# SCH_TRAFFIC_LIGHT.net
KiCad netlist of a schematic drawn in Altium Designer
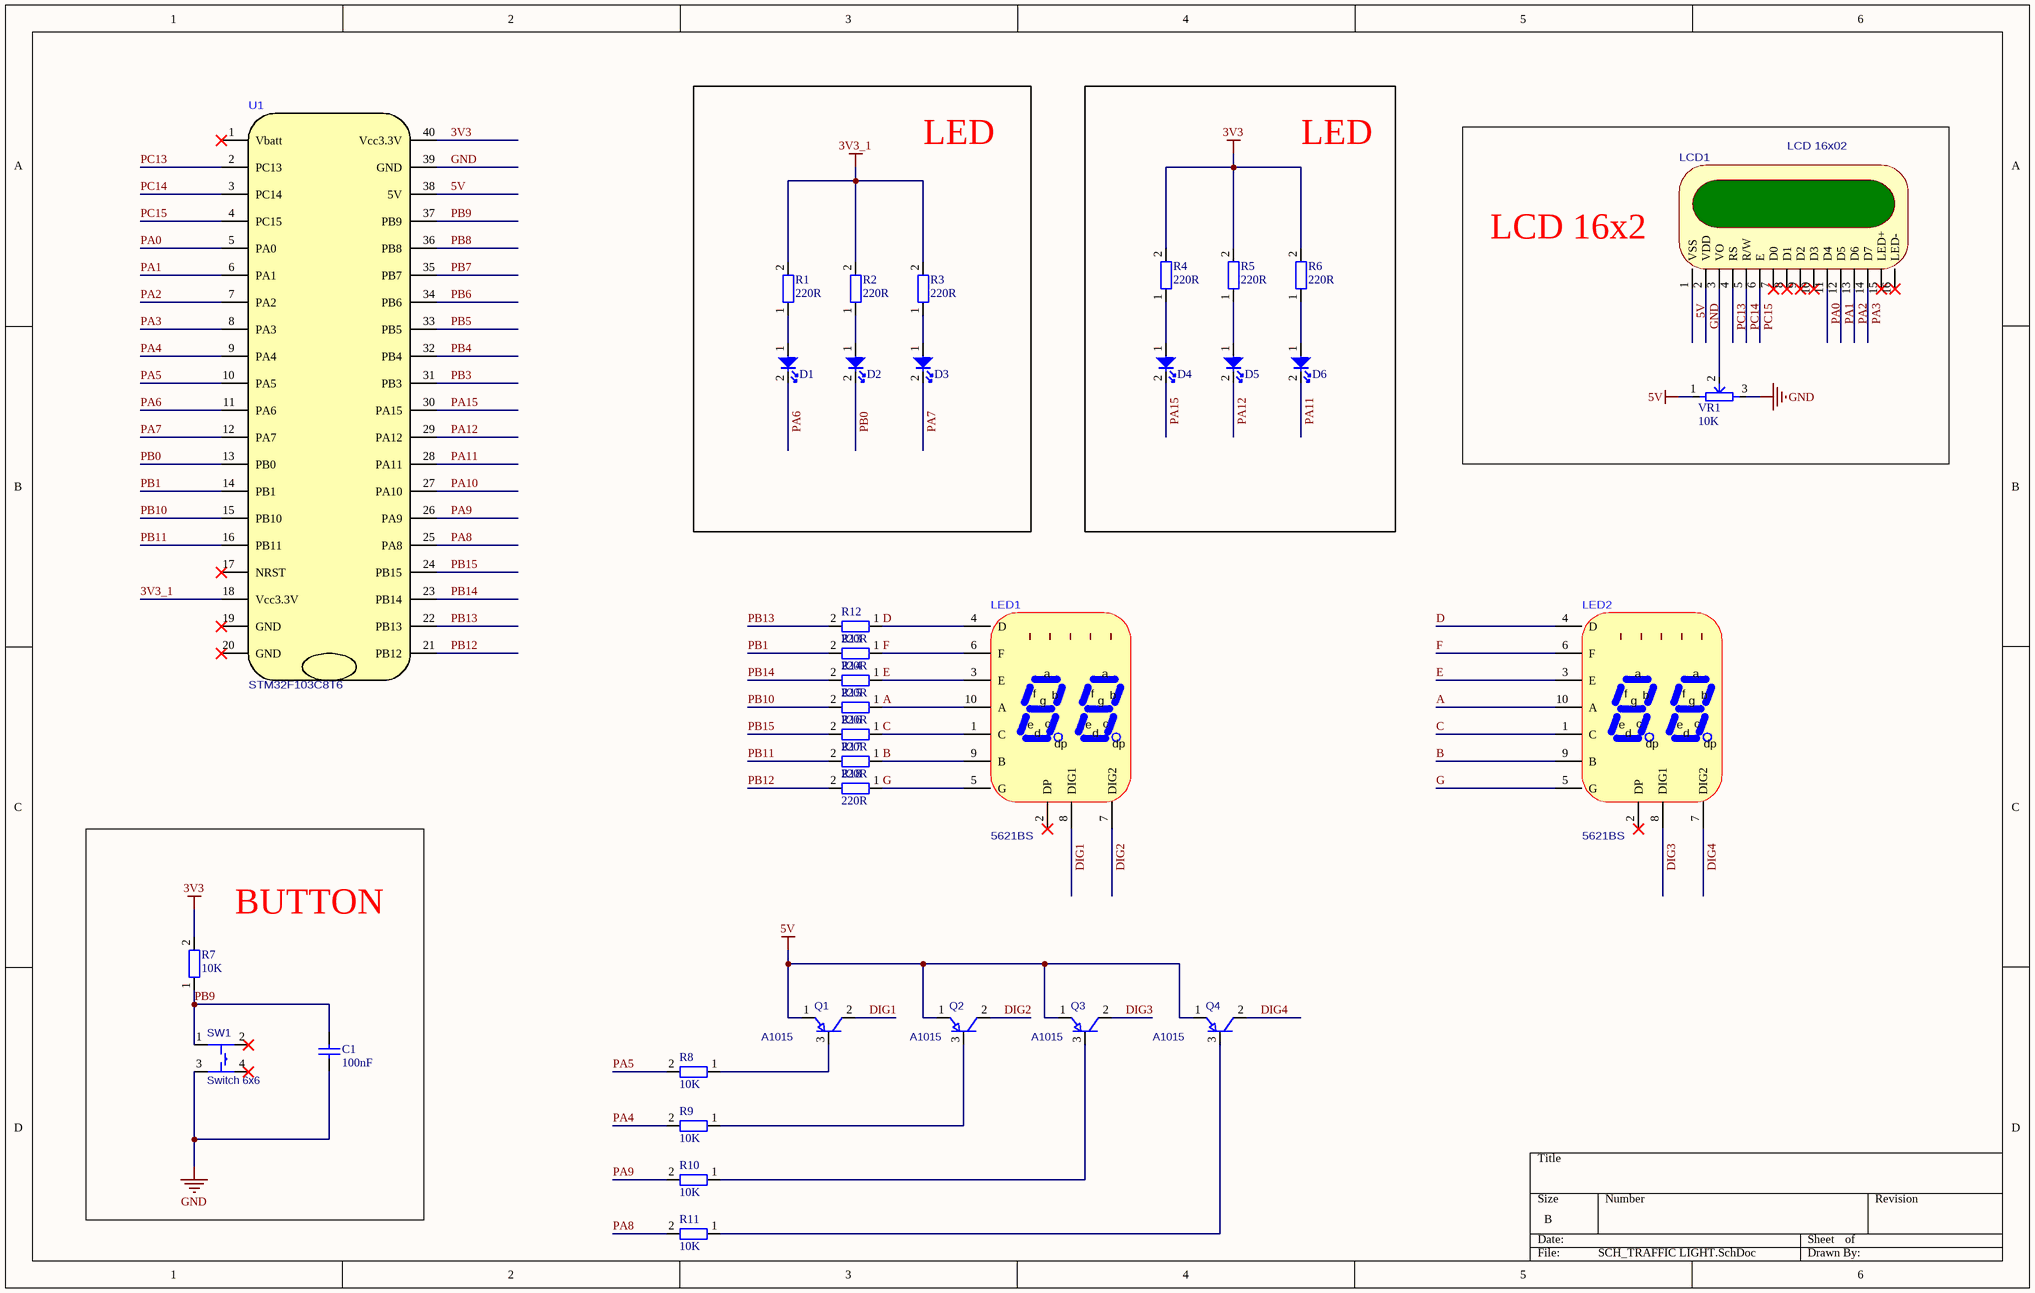
[diagram p0: SCH_TRAFFIC LIGHT.SchDoc]

(export (version "E")
  (design (tool "Eeschema 10.0.6"))
  (components
    (comp (ref "C1")
      (value "100nF")
      (footprint "CN1.5")
      (description "0805 Multilayer Ceramic Capacitors MLCC - SMD/SMT ROHS")
      (libsource (lib "SCH_AES_Library") (part "CAP 0805 50V 10%"))
    )
    (comp (ref "D1")
      (value "LED")
      (footprint "LED-3")
      (description "Emerald 0805 Light Emitting Diodes (LED) ROHS")
      (libsource (lib "SCH_AES_Library") (part "LED SMD 0805"))
    )
    (comp (ref "D2")
      (value "LED")
      (footprint "LED-3")
      (description "Emerald 0805 Light Emitting Diodes (LED) ROHS")
      (libsource (lib "SCH_AES_Library") (part "LED SMD 0805"))
    )
    (comp (ref "D3")
      (value "LED")
      (footprint "LED-3")
      (description "Emerald 0805 Light Emitting Diodes (LED) ROHS")
      (libsource (lib "SCH_AES_Library") (part "LED SMD 0805"))
    )
    (comp (ref "D4")
      (value "LED")
      (footprint "LED-3")
      (description "Emerald 0805 Light Emitting Diodes (LED) ROHS")
      (libsource (lib "SCH_AES_Library") (part "LED SMD 0805"))
    )
    (comp (ref "D5")
      (value "LED")
      (footprint "LED-3")
      (description "Emerald 0805 Light Emitting Diodes (LED) ROHS")
      (libsource (lib "SCH_AES_Library") (part "LED SMD 0805"))
    )
    (comp (ref "D6")
      (value "LED")
      (footprint "LED-3")
      (description "Emerald 0805 Light Emitting Diodes (LED) ROHS")
      (libsource (lib "SCH_AES_Library") (part "LED SMD 0805"))
    )
    (comp (ref "LCD1")
      (value "LCD 16x02")
      (footprint "LCD DISPLAYS 16X2")
      (description "LCD Displays Modules 16x02 5V ROHS")
      (libsource (lib "SCH_AES_Library") (part "LCD DISPLAYS 16x02"))
    )
    (comp (ref "LED1")
      (value "5621BS")
      (footprint "LED 7 SEG-2 0.56 inch")
      (libsource (lib "SCH_AES_Library") (part "LED 7 SEG -2 0.56 inch"))
    )
    (comp (ref "LED2")
      (value "5621BS")
      (footprint "LED 7 SEG-2 0.56 inch")
      (libsource (lib "SCH_AES_Library") (part "LED 7 SEG -2 0.56 inch"))
    )
    (comp (ref "Q1")
      (value "A1015")
      (footprint "TO-92")
      (fields
        (field (name "BOM_MANUFACTURER PART") "2SA1015-TA")
        (field (name "BOM_SUPPLIER PART") "C2084")
        (field (name "CONTRIBUTOR") "立创EDA官方封装库")
      )
      (libsource (lib "SCH_AES_Library") (part "TRANSISTOR HOLD PNP"))
    )
    (comp (ref "Q2")
      (value "A1015")
      (footprint "TO-92")
      (fields
        (field (name "BOM_MANUFACTURER PART") "2SA1015-TA")
        (field (name "BOM_SUPPLIER PART") "C2084")
        (field (name "CONTRIBUTOR") "立创EDA官方封装库")
      )
      (libsource (lib "SCH_AES_Library") (part "TRANSISTOR HOLD PNP"))
    )
    (comp (ref "Q3")
      (value "A1015")
      (footprint "TO-92")
      (fields
        (field (name "BOM_MANUFACTURER PART") "2SA1015-TA")
        (field (name "BOM_SUPPLIER PART") "C2084")
        (field (name "CONTRIBUTOR") "立创EDA官方封装库")
      )
      (libsource (lib "SCH_AES_Library") (part "TRANSISTOR HOLD PNP"))
    )
    (comp (ref "Q4")
      (value "A1015")
      (footprint "TO-92")
      (fields
        (field (name "BOM_MANUFACTURER PART") "2SA1015-TA")
        (field (name "BOM_SUPPLIER PART") "C2084")
        (field (name "CONTRIBUTOR") "立创EDA官方封装库")
      )
      (libsource (lib "SCH_AES_Library") (part "TRANSISTOR HOLD PNP"))
    )
    (comp (ref "R1")
      (value "220R")
      (footprint "RES CHIPS HOLD 1/4W TYPE 350MIL")
      (libsource (lib "SCH_AES_Library") (part "RES HOLD 1%"))
    )
    (comp (ref "R2")
      (value "220R")
      (footprint "RES CHIPS HOLD 1/4W TYPE 350MIL")
      (libsource (lib "SCH_AES_Library") (part "RES HOLD 1%"))
    )
    (comp (ref "R3")
      (value "220R")
      (footprint "RES CHIPS HOLD 1/4W TYPE 350MIL")
      (libsource (lib "SCH_AES_Library") (part "RES HOLD 1%"))
    )
    (comp (ref "R4")
      (value "220R")
      (footprint "RES CHIPS HOLD 1/4W TYPE 350MIL")
      (libsource (lib "SCH_AES_Library") (part "RES HOLD 1%"))
    )
    (comp (ref "R5")
      (value "220R")
      (footprint "RES CHIPS HOLD 1/4W TYPE 350MIL")
      (libsource (lib "SCH_AES_Library") (part "RES HOLD 1%"))
    )
    (comp (ref "R6")
      (value "220R")
      (footprint "RES CHIPS HOLD 1/4W TYPE 350MIL")
      (libsource (lib "SCH_AES_Library") (part "RES HOLD 1%"))
    )
    (comp (ref "R7")
      (value "10K")
      (footprint "RES CHIPS HOLD 1/4W TYPE 350MIL")
      (libsource (lib "SCH_AES_Library") (part "RES HOLD 1%"))
    )
    (comp (ref "R8")
      (value "10K")
      (footprint "RES CHIPS HOLD 1/4W TYPE 350MIL")
      (libsource (lib "SCH_AES_Library") (part "RES HOLD 1%"))
    )
    (comp (ref "R9")
      (value "10K")
      (footprint "RES CHIPS HOLD 1/4W TYPE 350MIL")
      (libsource (lib "SCH_AES_Library") (part "RES HOLD 1%"))
    )
    (comp (ref "R10")
      (value "10K")
      (footprint "RES CHIPS HOLD 1/4W TYPE 350MIL")
      (libsource (lib "SCH_AES_Library") (part "RES HOLD 1%"))
    )
    (comp (ref "R11")
      (value "10K")
      (footprint "RES CHIPS HOLD 1/4W TYPE 350MIL")
      (libsource (lib "SCH_AES_Library") (part "RES HOLD 1%"))
    )
    (comp (ref "R12")
      (value "220R")
      (footprint "RES CHIPS HOLD 1/4W TYPE 350MIL")
      (libsource (lib "SCH_AES_Library") (part "RES HOLD 1%"))
    )
    (comp (ref "R13")
      (value "220R")
      (footprint "RES CHIPS HOLD 1/4W TYPE 350MIL")
      (libsource (lib "SCH_AES_Library") (part "RES HOLD 1%"))
    )
    (comp (ref "R14")
      (value "220R")
      (footprint "RES CHIPS HOLD 1/4W TYPE 350MIL")
      (libsource (lib "SCH_AES_Library") (part "RES HOLD 1%"))
    )
    (comp (ref "R15")
      (value "220R")
      (footprint "RES CHIPS HOLD 1/4W TYPE 350MIL")
      (libsource (lib "SCH_AES_Library") (part "RES HOLD 1%"))
    )
    (comp (ref "R16")
      (value "220R")
      (footprint "RES CHIPS HOLD 1/4W TYPE 350MIL")
      (libsource (lib "SCH_AES_Library") (part "RES HOLD 1%"))
    )
    (comp (ref "R17")
      (value "220R")
      (footprint "RES CHIPS HOLD 1/4W TYPE 350MIL")
      (libsource (lib "SCH_AES_Library") (part "RES HOLD 1%"))
    )
    (comp (ref "R18")
      (value "220R")
      (footprint "RES CHIPS HOLD 1/4W TYPE 350MIL")
      (libsource (lib "SCH_AES_Library") (part "RES HOLD 1%"))
    )
    (comp (ref "SW1")
      (value "Switch 6x6")
      (footprint "SWITCHES TACTILE DIP 6X6x5 mm")
      (fields
        (field (name "BOM_MANUFACTURER PART") "B3F-1000")
        (field (name "BOM_SUPPLIER PART") "C93157")
        (field (name "CONTRIBUTOR") "LCSC")
      )
      (libsource (lib "SCH_AES_Library") (part "SWITCHS TACTILE DIP 6x6mm"))
    )
    (comp (ref "U1")
      (value "STM32F103C8T6")
      (footprint "MODULE STM32F103C8T6")
      (libsource (lib "SCH_AES_Library") (part "MODULE STM32F103C8T6"))
    )
    (comp (ref "VR1")
      (value "10K")
      (footprint "RES VARIABLE HOLE 3362P")
      (description "Plugin Variable Resistors/Potentiometers ROHS")
      (libsource (lib "SCH_AES_Library") (part "RES VARIABLE HOLD 3P"))
    )
  )
  (nets
    (net (code "1") (name "/A") (class "Default")
      (node (ref "LED1") (pin "10") (pinfunction "A_10") (pintype "passive"))
      (node (ref "LED2") (pin "10") (pinfunction "A_10") (pintype "passive"))
      (node (ref "R15") (pin "1") (pinfunction "1_1") (pintype "passive"))
    )
    (net (code "2") (name "/B") (class "Default")
      (node (ref "LED1") (pin "9") (pinfunction "B_9") (pintype "passive"))
      (node (ref "LED2") (pin "9") (pinfunction "B_9") (pintype "passive"))
      (node (ref "R17") (pin "1") (pinfunction "1_1") (pintype "passive"))
    )
    (net (code "3") (name "/C") (class "Default")
      (node (ref "LED1") (pin "1") (pinfunction "C_1") (pintype "passive"))
      (node (ref "LED2") (pin "1") (pinfunction "C_1") (pintype "passive"))
      (node (ref "R16") (pin "1") (pinfunction "1_1") (pintype "passive"))
    )
    (net (code "4") (name "/D") (class "Default")
      (node (ref "LED1") (pin "4") (pinfunction "D_4") (pintype "passive"))
      (node (ref "LED2") (pin "4") (pinfunction "D_4") (pintype "passive"))
      (node (ref "R12") (pin "1") (pinfunction "1_1") (pintype "passive"))
    )
    (net (code "5") (name "/DIG1") (class "Default")
      (node (ref "LED1") (pin "8") (pinfunction "DIG1_8") (pintype "passive"))
      (node (ref "Q1") (pin "2") (pinfunction "C_2") (pintype "passive"))
    )
    (net (code "6") (name "/DIG2") (class "Default")
      (node (ref "LED1") (pin "7") (pinfunction "DIG2_7") (pintype "passive"))
      (node (ref "Q2") (pin "2") (pinfunction "C_2") (pintype "passive"))
    )
    (net (code "7") (name "/DIG3") (class "Default")
      (node (ref "LED2") (pin "8") (pinfunction "DIG1_8") (pintype "passive"))
      (node (ref "Q3") (pin "2") (pinfunction "C_2") (pintype "passive"))
    )
    (net (code "8") (name "/DIG4") (class "Default")
      (node (ref "LED2") (pin "7") (pinfunction "DIG2_7") (pintype "passive"))
      (node (ref "Q4") (pin "2") (pinfunction "C_2") (pintype "passive"))
    )
    (net (code "9") (name "/E") (class "Default")
      (node (ref "LED1") (pin "3") (pinfunction "E_3") (pintype "passive"))
      (node (ref "LED2") (pin "3") (pinfunction "E_3") (pintype "passive"))
      (node (ref "R14") (pin "1") (pinfunction "1_1") (pintype "passive"))
    )
    (net (code "10") (name "/F") (class "Default")
      (node (ref "LED1") (pin "6") (pinfunction "F_6") (pintype "passive"))
      (node (ref "LED2") (pin "6") (pinfunction "F_6") (pintype "passive"))
      (node (ref "R13") (pin "1") (pinfunction "1_1") (pintype "passive"))
    )
    (net (code "11") (name "/G") (class "Default")
      (node (ref "LED1") (pin "5") (pinfunction "G_5") (pintype "passive"))
      (node (ref "LED2") (pin "5") (pinfunction "G_5") (pintype "passive"))
      (node (ref "R18") (pin "1") (pinfunction "1_1") (pintype "passive"))
    )
    (net (code "12") (name "/PA0") (class "Default")
      (node (ref "LCD1") (pin "11") (pinfunction "D4_11") (pintype "passive"))
      (node (ref "U1") (pin "5") (pinfunction "PA0_5") (pintype "passive"))
    )
    (net (code "13") (name "/PA1") (class "Default")
      (node (ref "LCD1") (pin "12") (pinfunction "D5_12") (pintype "passive"))
      (node (ref "U1") (pin "6") (pinfunction "PA1_6") (pintype "passive"))
    )
    (net (code "14") (name "/PA2") (class "Default")
      (node (ref "LCD1") (pin "13") (pinfunction "D6_13") (pintype "passive"))
      (node (ref "U1") (pin "7") (pinfunction "PA2_7") (pintype "passive"))
    )
    (net (code "15") (name "/PA3") (class "Default")
      (node (ref "LCD1") (pin "14") (pinfunction "D7_14") (pintype "passive"))
      (node (ref "U1") (pin "8") (pinfunction "PA3_8") (pintype "passive"))
    )
    (net (code "16") (name "/PA4") (class "Default")
      (node (ref "R9") (pin "2") (pinfunction "2_2") (pintype "passive"))
      (node (ref "U1") (pin "9") (pinfunction "PA4_9") (pintype "passive"))
    )
    (net (code "17") (name "/PA5") (class "Default")
      (node (ref "R8") (pin "2") (pinfunction "2_2") (pintype "passive"))
      (node (ref "U1") (pin "10") (pinfunction "PA5_10") (pintype "passive"))
    )
    (net (code "18") (name "/PA6") (class "Default")
      (node (ref "D1") (pin "2") (pinfunction "2_2") (pintype "passive"))
      (node (ref "U1") (pin "11") (pinfunction "PA6_11") (pintype "passive"))
    )
    (net (code "19") (name "/PA7") (class "Default")
      (node (ref "D3") (pin "2") (pinfunction "2_2") (pintype "passive"))
      (node (ref "U1") (pin "12") (pinfunction "PA7_12") (pintype "passive"))
    )
    (net (code "20") (name "/PA8") (class "Default")
      (node (ref "R11") (pin "2") (pinfunction "2_2") (pintype "passive"))
      (node (ref "U1") (pin "25") (pinfunction "PA8_25") (pintype "passive"))
    )
    (net (code "21") (name "/PA9") (class "Default")
      (node (ref "R10") (pin "2") (pinfunction "2_2") (pintype "passive"))
      (node (ref "U1") (pin "26") (pinfunction "PA9_26") (pintype "passive"))
    )
    (net (code "22") (name "/PA10") (class "Default")
      (node (ref "U1") (pin "27") (pinfunction "PA10_27") (pintype "passive"))
    )
    (net (code "23") (name "/PA11") (class "Default")
      (node (ref "D6") (pin "2") (pinfunction "2_2") (pintype "passive"))
      (node (ref "U1") (pin "28") (pinfunction "PA11_28") (pintype "passive"))
    )
    (net (code "24") (name "/PA12") (class "Default")
      (node (ref "D5") (pin "2") (pinfunction "2_2") (pintype "passive"))
      (node (ref "U1") (pin "29") (pinfunction "PA12_29") (pintype "passive"))
    )
    (net (code "25") (name "/PA15") (class "Default")
      (node (ref "D4") (pin "2") (pinfunction "2_2") (pintype "passive"))
      (node (ref "U1") (pin "30") (pinfunction "PA15_30") (pintype "passive"))
    )
    (net (code "26") (name "/PB0") (class "Default")
      (node (ref "D2") (pin "2") (pinfunction "2_2") (pintype "passive"))
      (node (ref "U1") (pin "13") (pinfunction "PB0_13") (pintype "passive"))
    )
    (net (code "27") (name "/PB1") (class "Default")
      (node (ref "R13") (pin "2") (pinfunction "2_2") (pintype "passive"))
      (node (ref "U1") (pin "14") (pinfunction "PB1_14") (pintype "passive"))
    )
    (net (code "28") (name "/PB3") (class "Default")
      (node (ref "U1") (pin "31") (pinfunction "PB3_31") (pintype "passive"))
    )
    (net (code "29") (name "/PB4") (class "Default")
      (node (ref "U1") (pin "32") (pinfunction "PB4_32") (pintype "passive"))
    )
    (net (code "30") (name "/PB5") (class "Default")
      (node (ref "U1") (pin "33") (pinfunction "PB5_33") (pintype "passive"))
    )
    (net (code "31") (name "/PB6") (class "Default")
      (node (ref "U1") (pin "34") (pinfunction "PB6_34") (pintype "passive"))
    )
    (net (code "32") (name "/PB7") (class "Default")
      (node (ref "U1") (pin "35") (pinfunction "PB7_35") (pintype "passive"))
    )
    (net (code "33") (name "/PB8") (class "Default")
      (node (ref "U1") (pin "36") (pinfunction "PB8_36") (pintype "passive"))
    )
    (net (code "34") (name "/PB9") (class "Default")
      (node (ref "C1") (pin "1") (pinfunction "1_1") (pintype "passive"))
      (node (ref "R7") (pin "1") (pinfunction "1_1") (pintype "passive"))
      (node (ref "SW1") (pin "1") (pinfunction "1_1") (pintype "passive"))
      (node (ref "U1") (pin "37") (pinfunction "PB9_37") (pintype "passive"))
    )
    (net (code "35") (name "/PB10") (class "Default")
      (node (ref "R15") (pin "2") (pinfunction "2_2") (pintype "passive"))
      (node (ref "U1") (pin "15") (pinfunction "PB10_15") (pintype "passive"))
    )
    (net (code "36") (name "/PB11") (class "Default")
      (node (ref "R17") (pin "2") (pinfunction "2_2") (pintype "passive"))
      (node (ref "U1") (pin "16") (pinfunction "PB11_16") (pintype "passive"))
    )
    (net (code "37") (name "/PB12") (class "Default")
      (node (ref "R18") (pin "2") (pinfunction "2_2") (pintype "passive"))
      (node (ref "U1") (pin "21") (pinfunction "PB12_21") (pintype "passive"))
    )
    (net (code "38") (name "/PB13") (class "Default")
      (node (ref "R12") (pin "2") (pinfunction "2_2") (pintype "passive"))
      (node (ref "U1") (pin "22") (pinfunction "PB13_22") (pintype "passive"))
    )
    (net (code "39") (name "/PB14") (class "Default")
      (node (ref "R14") (pin "2") (pinfunction "2_2") (pintype "passive"))
      (node (ref "U1") (pin "23") (pinfunction "PB14_23") (pintype "passive"))
    )
    (net (code "40") (name "/PB15") (class "Default")
      (node (ref "R16") (pin "2") (pinfunction "2_2") (pintype "passive"))
      (node (ref "U1") (pin "24") (pinfunction "PB15_24") (pintype "passive"))
    )
    (net (code "41") (name "/PC13") (class "Default")
      (node (ref "LCD1") (pin "4") (pinfunction "RS_4") (pintype "passive"))
      (node (ref "U1") (pin "2") (pinfunction "PC13_2") (pintype "passive"))
    )
    (net (code "42") (name "/PC14") (class "Default")
      (node (ref "LCD1") (pin "5") (pinfunction "R/W_5") (pintype "passive"))
      (node (ref "U1") (pin "3") (pinfunction "PC14_3") (pintype "passive"))
    )
    (net (code "43") (name "/PC15") (class "Default")
      (node (ref "LCD1") (pin "6") (pinfunction "E_6") (pintype "passive"))
      (node (ref "U1") (pin "4") (pinfunction "PC15_4") (pintype "passive"))
    )
    (net (code "44") (name "3V3") (class "Default")
      (node (ref "R4") (pin "2") (pinfunction "2_2") (pintype "passive"))
      (node (ref "R5") (pin "2") (pinfunction "2_2") (pintype "passive"))
      (node (ref "R6") (pin "2") (pinfunction "2_2") (pintype "passive"))
      (node (ref "R7") (pin "2") (pinfunction "2_2") (pintype "passive"))
      (node (ref "U1") (pin "40") (pinfunction "Vcc3.3V_40") (pintype "passive"))
    )
    (net (code "45") (name "3V3_1") (class "Default")
      (node (ref "R1") (pin "2") (pinfunction "2_2") (pintype "passive"))
      (node (ref "R2") (pin "2") (pinfunction "2_2") (pintype "passive"))
      (node (ref "R3") (pin "2") (pinfunction "2_2") (pintype "passive"))
      (node (ref "U1") (pin "18") (pinfunction "Vcc3.3V_18") (pintype "passive"))
    )
    (net (code "46") (name "5V") (class "Default")
      (node (ref "LCD1") (pin "1") (pinfunction "VSS_1") (pintype "passive"))
      (node (ref "Q1") (pin "1") (pinfunction "E_1") (pintype "passive"))
      (node (ref "Q2") (pin "1") (pinfunction "E_1") (pintype "passive"))
      (node (ref "Q3") (pin "1") (pinfunction "E_1") (pintype "passive"))
      (node (ref "Q4") (pin "1") (pinfunction "E_1") (pintype "passive"))
      (node (ref "U1") (pin "38") (pinfunction "5V_38") (pintype "passive"))
      (node (ref "VR1") (pin "1") (pinfunction "1_1") (pintype "passive"))
    )
    (net (code "47") (name "GND") (class "Default")
      (node (ref "C1") (pin "2") (pinfunction "2_2") (pintype "passive"))
      (node (ref "LCD1") (pin "2") (pinfunction "VDD_2") (pintype "passive"))
      (node (ref "SW1") (pin "3") (pinfunction "3_3") (pintype "passive"))
      (node (ref "U1") (pin "39") (pinfunction "GND_39") (pintype "passive"))
      (node (ref "VR1") (pin "3") (pinfunction "3_3") (pintype "passive"))
    )
    (net (code "48") (name "Net-(D1-Pad1)") (class "Default")
      (node (ref "D1") (pin "1") (pinfunction "1_1") (pintype "passive"))
      (node (ref "R1") (pin "1") (pinfunction "1_1") (pintype "passive"))
    )
    (net (code "49") (name "Net-(D2-Pad1)") (class "Default")
      (node (ref "D2") (pin "1") (pinfunction "1_1") (pintype "passive"))
      (node (ref "R2") (pin "1") (pinfunction "1_1") (pintype "passive"))
    )
    (net (code "50") (name "Net-(D3-Pad1)") (class "Default")
      (node (ref "D3") (pin "1") (pinfunction "1_1") (pintype "passive"))
      (node (ref "R3") (pin "1") (pinfunction "1_1") (pintype "passive"))
    )
    (net (code "51") (name "Net-(D4-Pad1)") (class "Default")
      (node (ref "D4") (pin "1") (pinfunction "1_1") (pintype "passive"))
      (node (ref "R4") (pin "1") (pinfunction "1_1") (pintype "passive"))
    )
    (net (code "52") (name "Net-(D5-Pad1)") (class "Default")
      (node (ref "D5") (pin "1") (pinfunction "1_1") (pintype "passive"))
      (node (ref "R5") (pin "1") (pinfunction "1_1") (pintype "passive"))
    )
    (net (code "53") (name "Net-(D6-Pad1)") (class "Default")
      (node (ref "D6") (pin "1") (pinfunction "1_1") (pintype "passive"))
      (node (ref "R6") (pin "1") (pinfunction "1_1") (pintype "passive"))
    )
    (net (code "54") (name "Net-(LCD1-VO)") (class "Default")
      (node (ref "LCD1") (pin "3") (pinfunction "VO_3") (pintype "passive"))
      (node (ref "VR1") (pin "2") (pinfunction "2_2") (pintype "passive"))
    )
    (net (code "55") (name "Net-(Q1-B)") (class "Default")
      (node (ref "Q1") (pin "3") (pinfunction "B_3") (pintype "passive"))
      (node (ref "R8") (pin "1") (pinfunction "1_1") (pintype "passive"))
    )
    (net (code "56") (name "Net-(Q2-B)") (class "Default")
      (node (ref "Q2") (pin "3") (pinfunction "B_3") (pintype "passive"))
      (node (ref "R9") (pin "1") (pinfunction "1_1") (pintype "passive"))
    )
    (net (code "57") (name "Net-(Q3-B)") (class "Default")
      (node (ref "Q3") (pin "3") (pinfunction "B_3") (pintype "passive"))
      (node (ref "R10") (pin "1") (pinfunction "1_1") (pintype "passive"))
    )
    (net (code "58") (name "Net-(Q4-B)") (class "Default")
      (node (ref "Q4") (pin "3") (pinfunction "B_3") (pintype "passive"))
      (node (ref "R11") (pin "1") (pinfunction "1_1") (pintype "passive"))
    )
    (net (code "59") (name "unconnected-(LCD1-D0-Pad7)") (class "Default")
      (node (ref "LCD1") (pin "7") (pinfunction "D0_7") (pintype "passive+no_connect"))
    )
    (net (code "60") (name "unconnected-(LCD1-D1-Pad8)") (class "Default")
      (node (ref "LCD1") (pin "8") (pinfunction "D1_8") (pintype "passive+no_connect"))
    )
    (net (code "61") (name "unconnected-(LCD1-D2-Pad9)") (class "Default")
      (node (ref "LCD1") (pin "9") (pinfunction "D2_9") (pintype "passive+no_connect"))
    )
    (net (code "62") (name "unconnected-(LCD1-D3-Pad10)") (class "Default")
      (node (ref "LCD1") (pin "10") (pinfunction "D3_10") (pintype "passive+no_connect"))
    )
    (net (code "63") (name "unconnected-(LCD1-LED+-Pad15)") (class "Default")
      (node (ref "LCD1") (pin "15") (pinfunction "LED+_15") (pintype "passive+no_connect"))
    )
    (net (code "64") (name "unconnected-(LCD1-LED--Pad16)") (class "Default")
      (node (ref "LCD1") (pin "16") (pinfunction "LED-_16") (pintype "passive+no_connect"))
    )
    (net (code "65") (name "unconnected-(LED1-DP-Pad2)") (class "Default")
      (node (ref "LED1") (pin "2") (pinfunction "DP_2") (pintype "passive+no_connect"))
    )
    (net (code "66") (name "unconnected-(LED2-DP-Pad2)") (class "Default")
      (node (ref "LED2") (pin "2") (pinfunction "DP_2") (pintype "passive+no_connect"))
    )
    (net (code "67") (name "unconnected-(SW1-Pad2)") (class "Default")
      (node (ref "SW1") (pin "2") (pinfunction "2_2") (pintype "passive+no_connect"))
    )
    (net (code "68") (name "unconnected-(SW1-Pad4)") (class "Default")
      (node (ref "SW1") (pin "4") (pinfunction "4_4") (pintype "passive+no_connect"))
    )
    (net (code "69") (name "unconnected-(U1-GND-Pad19)") (class "Default")
      (node (ref "U1") (pin "19") (pinfunction "GND_19") (pintype "passive+no_connect"))
    )
    (net (code "70") (name "unconnected-(U1-GND-Pad20)") (class "Default")
      (node (ref "U1") (pin "20") (pinfunction "GND_20") (pintype "passive+no_connect"))
    )
    (net (code "71") (name "unconnected-(U1-NRST-Pad17)") (class "Default")
      (node (ref "U1") (pin "17") (pinfunction "NRST_17") (pintype "passive+no_connect"))
    )
    (net (code "72") (name "unconnected-(U1-Vbatt-Pad1)") (class "Default")
      (node (ref "U1") (pin "1") (pinfunction "Vbatt_1") (pintype "passive+no_connect"))
    )
  )
)
